# MAZ000177_-_Diagrama_el_ctrico.net
KiCad netlist of a schematic drawn in Altium Designer
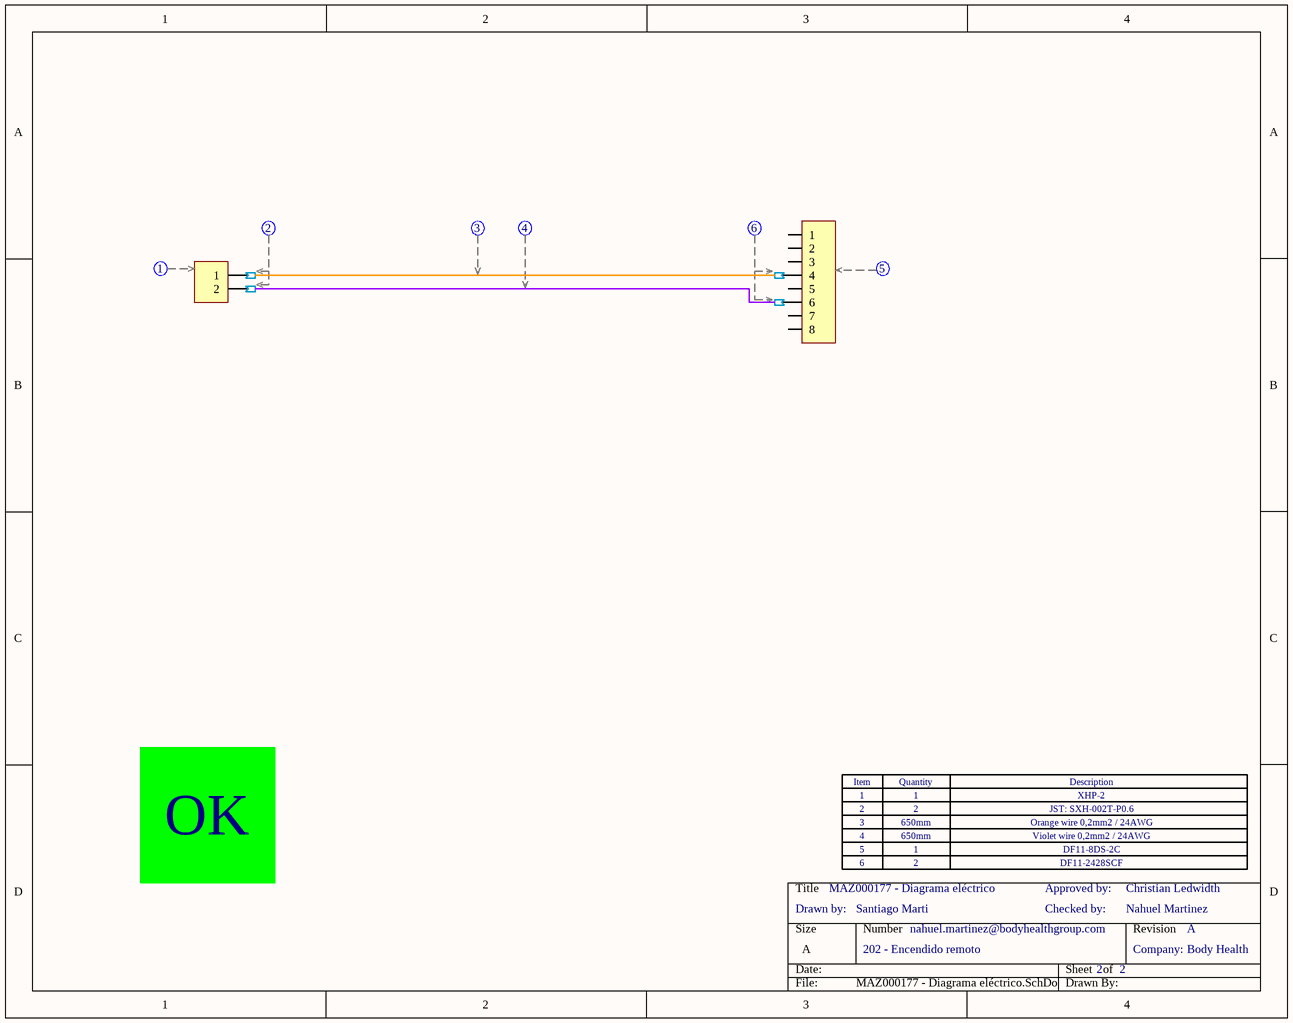
[diagram p0: MAZ000177 - Diagrama eléctrico.SchDoc]

(export (version "E")
  (design (tool "Eeschema 10.0.6"))
  (components
    (comp (ref "Con1")
      (value "DF11-8DS-2C")
      (description "CONN SOCKET 8POS 2MM DUAL CRIMP")
      (libsource (lib "") (part "DF11-8DS-2C_1"))
    )
    (comp (ref "Con2")
      (value "XHP-2")
      (description "CONN HOUSING 2.5MM 2POS")
      (libsource (lib "LibreriaParaPlanos") (part "XHP-2"))
    )
    (comp (ref "Soc1")
      (value "sock_XHP_SXH-002T-P0.6")
      (description "CONN SOCKET 26-30AWG CRIMP TIN")
      (libsource (lib "LibreriaParaPlanos") (part "sock_XHP_SXH-002T-P0.6"))
    )
    (comp (ref "Soc2")
      (value "sock_XHP_SXH-002T-P0.6")
      (description "CONN SOCKET 26-30AWG CRIMP TIN")
      (libsource (lib "LibreriaParaPlanos") (part "sock_XHP_SXH-002T-P0.6"))
    )
    (comp (ref "Soc3")
      (value "sock_XHP_SXH-002T-P0.6")
      (description "CONN SOCKET 26-30AWG CRIMP TIN")
      (libsource (lib "LibreriaParaPlanos") (part "sock_XHP_SXH-002T-P0.6"))
    )
    (comp (ref "Soc4")
      (value "sock_DF11-2428SCF")
      (description "CONN SOCKET 18-24AWG CRIMP TIN")
      (libsource (lib "LibreriaParaPlanos") (part "sock_DF11-2428SCF"))
    )
    (comp (ref "Soc5")
      (value "sock_DF11-2428SCF")
      (description "CONN SOCKET 18-24AWG CRIMP TIN")
      (libsource (lib "LibreriaParaPlanos") (part "sock_DF11-2428SCF"))
    )
    (comp (ref "Zoc1")
      (value "Zócalo_Header")
      (description "Header para el zócalo de referencias")
      (libsource (lib "LibreriaParaPlanos") (part "Zócalo_Header"))
    )
    (comp (ref "Zoc2")
      (value "Zócalo_Item")
      (description "Ítem para el zócalo de referencias")
      (libsource (lib "LibreriaParaPlanos") (part "Zócalo_Item"))
    )
    (comp (ref "Zoc3")
      (value "Zócalo_Item")
      (description "Ítem para el zócalo de referencias")
      (libsource (lib "LibreriaParaPlanos") (part "Zócalo_Item"))
    )
    (comp (ref "Zoc4")
      (value "Zócalo_Item")
      (description "Ítem para el zócalo de referencias")
      (libsource (lib "LibreriaParaPlanos") (part "Zócalo_Item"))
    )
    (comp (ref "Zoc5")
      (value "Zócalo_Item")
      (description "Ítem para el zócalo de referencias")
      (libsource (lib "LibreriaParaPlanos") (part "Zócalo_Item"))
    )
    (comp (ref "Zoc6")
      (value "Zócalo_Item")
      (description "Ítem para el zócalo de referencias")
      (libsource (lib "LibreriaParaPlanos") (part "Zócalo_Item"))
    )
    (comp (ref "Zoc7")
      (value "Zócalo_Item")
      (description "Ítem para el zócalo de referencias")
      (libsource (lib "LibreriaParaPlanos") (part "Zócalo_Item"))
    )
  )
  (nets
    (net (code "1") (name "Net-(Con1-Pad4)") (class "Default")
      (node (ref "Con1") (pin "4") (pinfunction "4_4") (pintype "passive"))
      (node (ref "Soc4") (pin "0") (pinfunction "0_0") (pintype "passive"))
    )
    (net (code "2") (name "Net-(Con1-Pad6)") (class "Default")
      (node (ref "Con1") (pin "6") (pinfunction "6_6") (pintype "passive"))
      (node (ref "Soc5") (pin "0") (pinfunction "0_0") (pintype "passive"))
    )
    (net (code "3") (name "Net-(Con2-Pad1)") (class "Default")
      (node (ref "Con2") (pin "1") (pinfunction "1_1") (pintype "passive"))
      (node (ref "Soc1") (pin "0") (pinfunction "0_0") (pintype "passive"))
    )
    (net (code "4") (name "Net-(Con2-Pad2)") (class "Default")
      (node (ref "Con2") (pin "2") (pinfunction "2_2") (pintype "passive"))
      (node (ref "Soc2") (pin "0") (pinfunction "0_0") (pintype "passive"))
    )
    (net (code "5") (name "Net-(Soc1-Pad1)") (class "Default")
      (node (ref "Soc1") (pin "1") (pinfunction "1_1") (pintype "passive"))
      (node (ref "Soc4") (pin "1") (pinfunction "1_1") (pintype "passive"))
    )
    (net (code "6") (name "Net-(Soc2-Pad1)") (class "Default")
      (node (ref "Soc2") (pin "1") (pinfunction "1_1") (pintype "passive"))
      (node (ref "Soc5") (pin "1") (pinfunction "1_1") (pintype "passive"))
    )
    (net (code "7") (name "unconnected-(Con1-Pad1)") (class "Default")
      (node (ref "Con1") (pin "1") (pinfunction "1_1") (pintype "passive"))
    )
    (net (code "8") (name "unconnected-(Con1-Pad2)") (class "Default")
      (node (ref "Con1") (pin "2") (pinfunction "2_2") (pintype "passive"))
    )
    (net (code "9") (name "unconnected-(Con1-Pad3)") (class "Default")
      (node (ref "Con1") (pin "3") (pinfunction "3_3") (pintype "passive"))
    )
    (net (code "10") (name "unconnected-(Con1-Pad5)") (class "Default")
      (node (ref "Con1") (pin "5") (pinfunction "5_5") (pintype "passive"))
    )
    (net (code "11") (name "unconnected-(Con1-Pad7)") (class "Default")
      (node (ref "Con1") (pin "7") (pinfunction "7_7") (pintype "passive"))
    )
    (net (code "12") (name "unconnected-(Con1-Pad8)") (class "Default")
      (node (ref "Con1") (pin "8") (pinfunction "8_8") (pintype "passive"))
    )
  )
)
